# MCU.net
KiCad netlist of a schematic drawn in Altium Designer
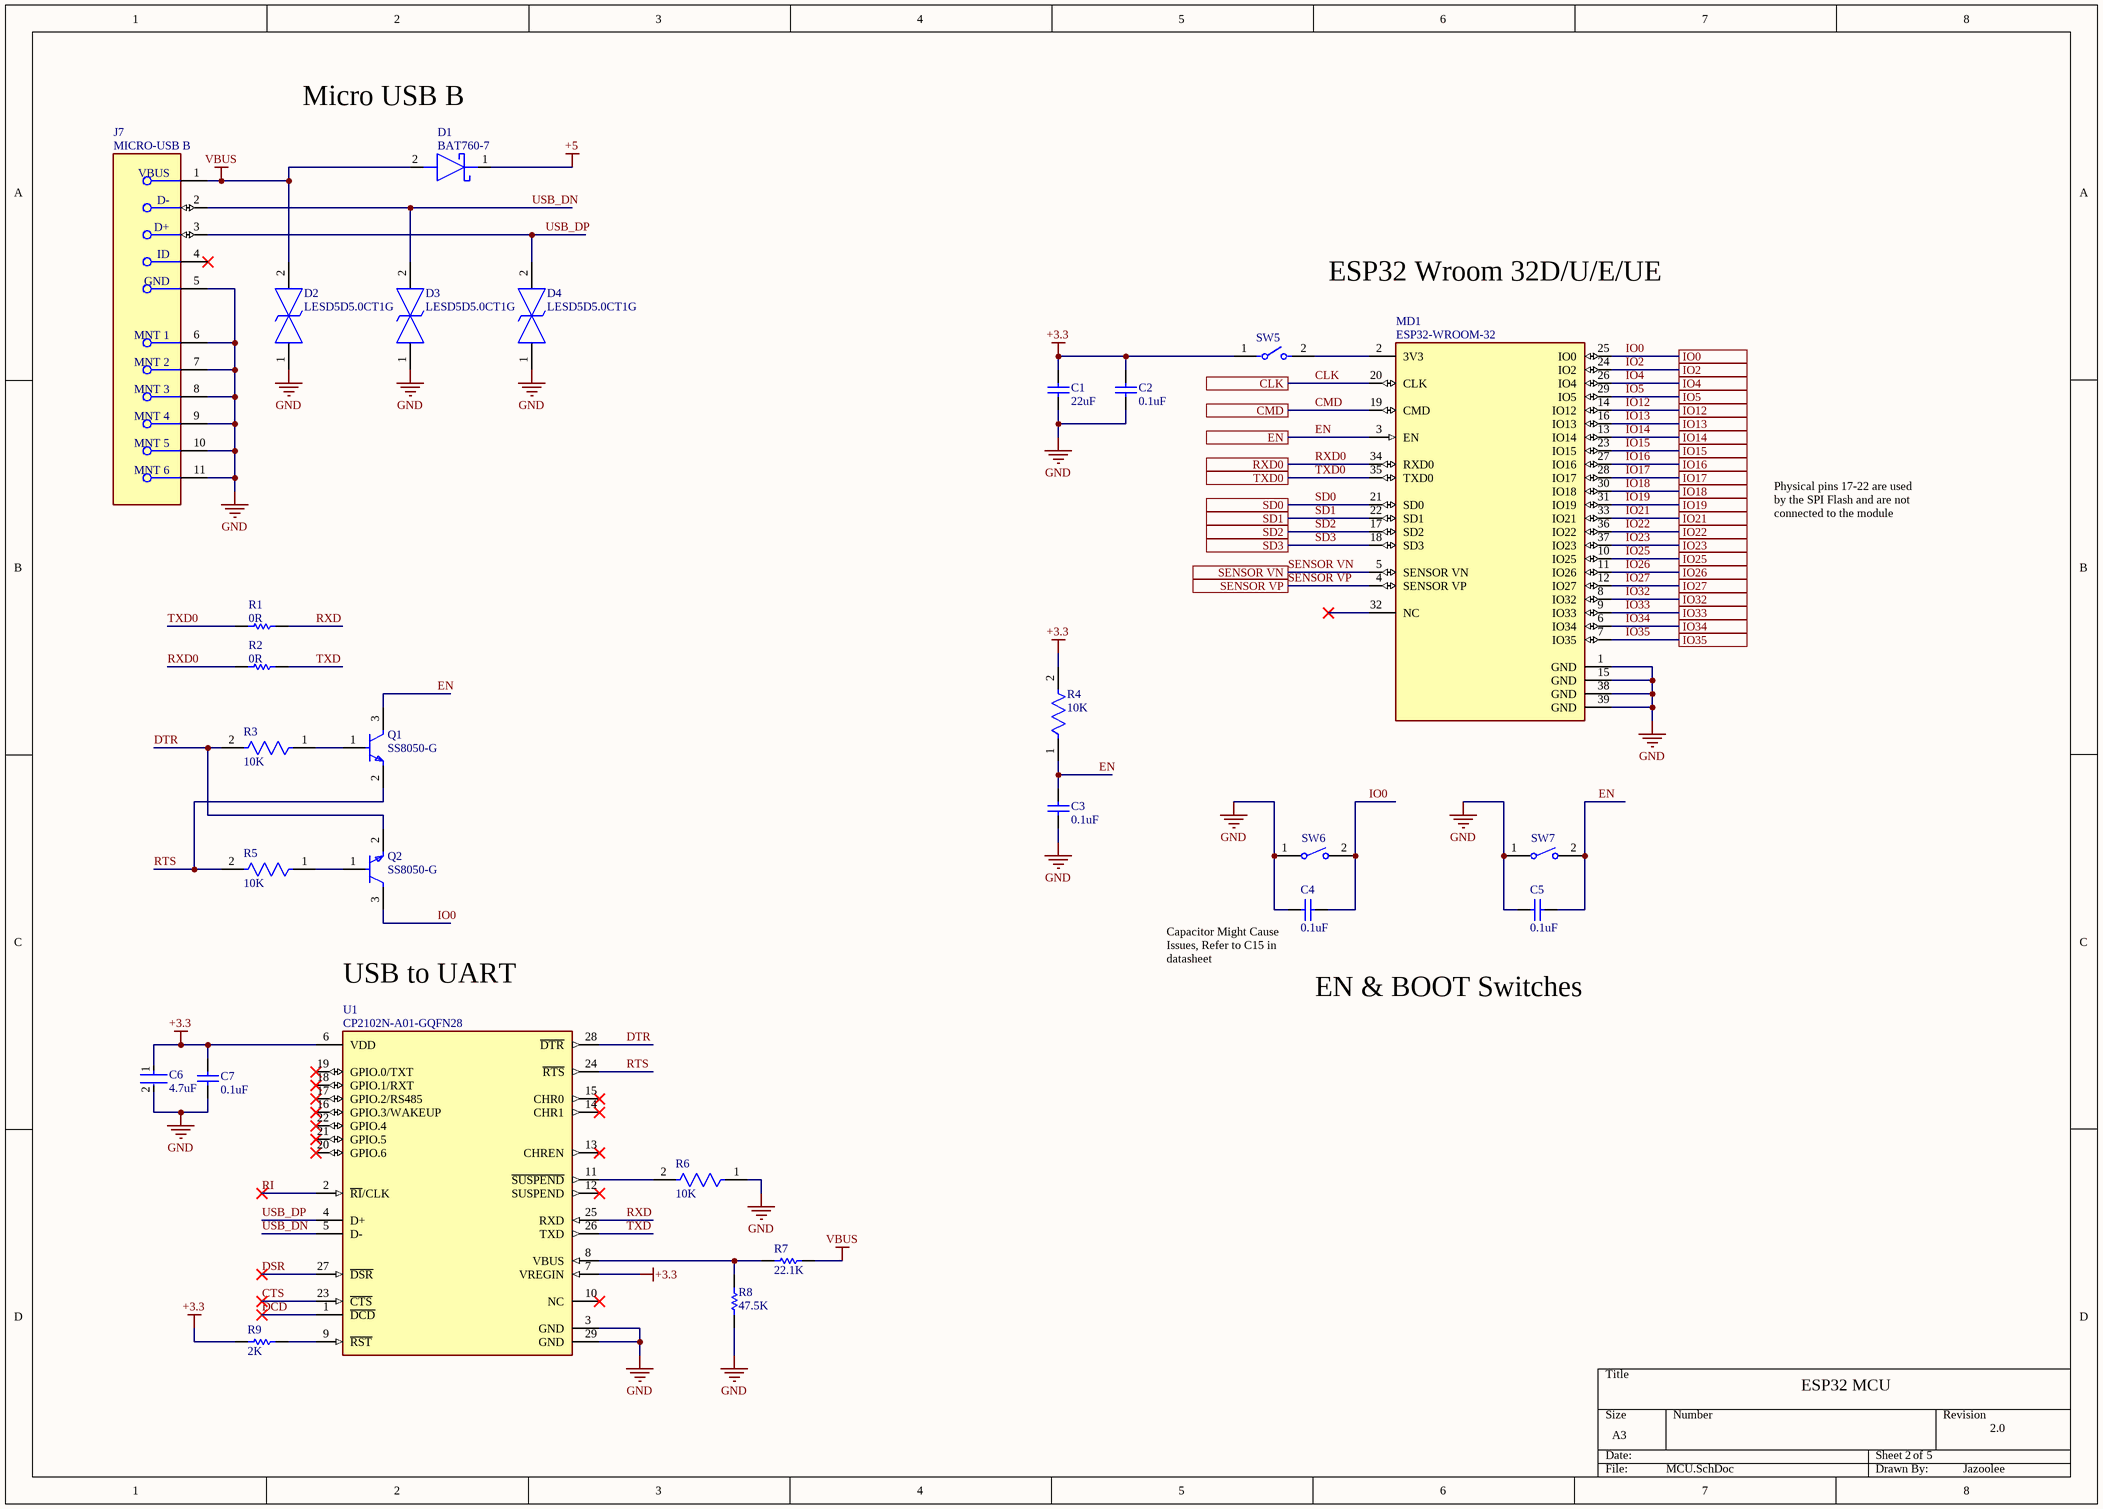
[diagram p0: MCU.SchDoc]

(export (version "E")
  (design (tool "Eeschema 10.0.6"))
  (components
    (comp (ref "C1")
      (value "22uF")
      (footprint "CAPC2014X150X70ML20")
      (description "22uF 10V 20% Tantalum 0805")
      (fields
        (field (name "PART NUMBER") "TACR226M010XTA")
        (field (name "MANUFACTURER") "AVX Interconnect / Elco")
      )
      (libsource (lib "Altium Content Vault") (part "CAP"))
    )
    (comp (ref "C2")
      (value "0.1uF")
      (footprint "CAPC2013X140X50LL20T25")
      (description "100nF 0805 Ceramic 50V 10%")
      (fields
        (field (name "MANUFACTURER") "AVX Interconnect / Elco")
        (field (name "PART NUMBER") "08055F104KAT2A")
      )
      (libsource (lib "Altium Content Vault") (part "CAP"))
    )
    (comp (ref "C3")
      (value "0.1uF")
      (footprint "CAPC2013X140X50LL20T25")
      (description "100nF 0805 Ceramic 50V 10%")
      (fields
        (field (name "MANUFACTURER") "AVX Interconnect / Elco")
        (field (name "PART NUMBER") "08055F104KAT2A")
      )
      (libsource (lib "Altium Content Vault") (part "CAP"))
    )
    (comp (ref "C4")
      (value "0.1uF")
      (footprint "CAPC2013X140X50LL20T25")
      (description "100nF 0805 Ceramic 50V 10%")
      (fields
        (field (name "MANUFACTURER") "AVX Interconnect / Elco")
        (field (name "PART NUMBER") "08055F104KAT2A")
      )
      (libsource (lib "Altium Content Vault") (part "CAP"))
    )
    (comp (ref "C5")
      (value "0.1uF")
      (footprint "CAPC2013X140X50LL20T25")
      (description "100nF 0805 Ceramic 50V 10%")
      (fields
        (field (name "MANUFACTURER") "AVX Interconnect / Elco")
        (field (name "PART NUMBER") "08055F104KAT2A")
      )
      (libsource (lib "Altium Content Vault") (part "CAP"))
    )
    (comp (ref "C6")
      (value "CL21A475KQFNNNF")
      (footprint "FP-CL21-IPC_B")
      (description "CL21 Series 0805 4.7uF 6.3V ±10% Tolerance X5R Multilayer Ceramic Chip Capacitor")
      (fields (field (name "CAPACITANCE") "4.7uF") (field (name "TOLERANCE") "10%"))
      (libsource (lib "Altium Content Vault") (part "b4654b650e69147ec39a6b967a45e02"))
    )
    (comp (ref "C7")
      (value "0.1uF")
      (footprint "CAPC2013X140X50LL20T25")
      (description "100nF 0805 Ceramic 50V 10%")
      (fields
        (field (name "MANUFACTURER") "AVX Interconnect / Elco")
        (field (name "PART NUMBER") "08055F104KAT2A")
      )
      (libsource (lib "Altium Content Vault") (part "CAP"))
    )
    (comp (ref "D1")
      (value "BAT760-7")
      (footprint "SamacSys:SOD2512X110N")
      (description "Schottky Diode")
      (fields
        (field (name "MANUFACTURER_PART_NUMBER") "BAT760,115")
        (field (name "MOUSER PART NUMBER") "771-BAT760-T/R")
      )
      (libsource (lib "*") (part "BAT760,115"))
    )
    (comp (ref "D2")
      (value "LESD5D5.0CT1G")
      (footprint "SamacSys:LESD5D50CT1G")
      (description "TVS Diode (Bi-directional)")
      (libsource (lib "SamacSys") (part "LESD5D5.0CT1G"))
    )
    (comp (ref "D3")
      (value "LESD5D5.0CT1G")
      (footprint "SamacSys:LESD5D50CT1G")
      (description "TVS Diode (Bi-directional)")
      (libsource (lib "SamacSys") (part "LESD5D5.0CT1G"))
    )
    (comp (ref "D4")
      (value "LESD5D5.0CT1G")
      (footprint "SamacSys:LESD5D50CT1G")
      (description "TVS Diode (Bi-directional)")
      (libsource (lib "SamacSys") (part "LESD5D5.0CT1G"))
    )
    (comp (ref "J7")
      (value "MICRO-USB B")
      (footprint "FP-473460001-MFG")
      (description "USB - micro B USB 2.0 Receptacle Connector 5 Position Surface Mount, Right Angle")
      (fields (field (name "OCTOPART") "https://octopart.com/47346-0001-molex-7164928"))
      (libsource (lib "Altium Content Vault") (part "53ae1f1d9b557310b43ca686e5bb76a"))
    )
    (comp (ref "MD1")
      (value "ESP32-WROOM-32")
      (footprint "FP-ESP32-WROOM-32-MFG")
      (description "RX TXRX MOD WIFI SURFACE MOUNT")
      (libsource (lib "Altium Content Vault") (part "ee866abf0b6c51247b7f5cdebf2f250"))
    )
    (comp (ref "Q1")
      (value "SS8050-G")
      (footprint "FP-SS8050-G-MFG")
      (description "NPN TRANSISTOR 1.5A 40V SOT-23 R")
      (libsource (lib "Altium Content Vault") (part "2a1388f82443b098dcd57d24ac7632d"))
    )
    (comp (ref "Q2")
      (value "SS8050-G")
      (footprint "FP-SS8050-G-MFG")
      (description "NPN TRANSISTOR 1.5A 40V SOT-23 R")
      (libsource (lib "Altium Content Vault") (part "2a1388f82443b098dcd57d24ac7632d"))
    )
    (comp (ref "R1")
      (value "0R")
      (footprint "RESC2013X60X35LL10T20")
      (description "Chip Resistor, 0 Ohm, +/- 5%, 125 mW, -55 to 155 degC, 0805 (2012 Metric), RoHS, Tape and Reel")
      (fields (field (name "MANUFACTURER") "Yageo") (field (name "Comment") "RC0805JR-100RL"))
      (libsource (lib "Altium Content Vault") (part "RES-2"))
    )
    (comp (ref "R2")
      (value "0R")
      (footprint "RESC2013X60X35LL10T20")
      (description "Chip Resistor, 0 Ohm, +/- 5%, 125 mW, -55 to 155 degC, 0805 (2012 Metric), RoHS, Tape and Reel")
      (fields (field (name "MANUFACTURER") "Yageo") (field (name "Comment") "RC0805JR-100RL"))
      (libsource (lib "Altium Content Vault") (part "RES-2"))
    )
    (comp (ref "R3")
      (value "RMCF0805JT10K0")
      (footprint "FP-RMCF0805-IPC_A")
      (description "10kΩ ±5% 0.125W 0805 Thick Film Chip Resistor AEC-Q200 compliant")
      (fields (field (name "RESISTANCE") "10K") (field (name "TOLERANCE") "5%"))
      (libsource (lib "Altium Content Vault") (part "1029c3af85768c4190bb7ad29bc67b5"))
    )
    (comp (ref "R4")
      (value "RMCF0805JT10K0")
      (footprint "FP-RMCF0805-IPC_A")
      (description "10kΩ ±5% 0.125W 0805 Thick Film Chip Resistor AEC-Q200 compliant")
      (fields (field (name "RESISTANCE") "10K") (field (name "TOLERANCE") "5%"))
      (libsource (lib "Altium Content Vault") (part "1029c3af85768c4190bb7ad29bc67b5"))
    )
    (comp (ref "R5")
      (value "RMCF0805JT10K0")
      (footprint "FP-RMCF0805-IPC_A")
      (description "10kΩ ±5% 0.125W 0805 Thick Film Chip Resistor AEC-Q200 compliant")
      (fields (field (name "RESISTANCE") "10K") (field (name "TOLERANCE") "5%"))
      (libsource (lib "Altium Content Vault") (part "1029c3af85768c4190bb7ad29bc67b5"))
    )
    (comp (ref "R6")
      (value "RMCF0805JT10K0")
      (footprint "FP-RMCF0805-IPC_A")
      (description "10kΩ ±5% 0.125W 0805 Thick Film Chip Resistor AEC-Q200 compliant")
      (fields (field (name "RESISTANCE") "10K") (field (name "TOLERANCE") "5%"))
      (libsource (lib "Altium Content Vault") (part "1029c3af85768c4190bb7ad29bc67b5"))
    )
    (comp (ref "R7")
      (value "22.1K")
      (footprint "RESC2013X50X30LL20T20")
      (description "22.1K 0805 5%")
      (fields (field (name "MANUFACTURER") "Vishay Dale") (field (name "PART NUMBER") "CRCW080522K1FKTA"))
      (libsource (lib "Altium Content Vault") (part "RES"))
    )
    (comp (ref "R8")
      (value "47.5K")
      (footprint "RESC2013X70X40NL20T20")
      (description "47.5K 0805 5%")
      (fields (field (name "PART NUMBER") "ERJ-6ENF4752V") (field (name "MANUFACTURER") "Panasonic"))
      (libsource (lib "Altium Content Vault") (part "RES"))
    )
    (comp (ref "R9")
      (value "2K")
      (footprint "RESC2013X60X35LL10T20")
      (fields (field (name "PART NUMBER") "RT0805FRE072KL") (field (name "MANUFACTURER") "Yageo"))
      (libsource (lib "Altium Content Vault") (part "RES"))
    )
    (comp (ref "SW5")
      (value "BD01")
      (footprint "FP-BD01-MFG")
      (description "SWITCH SLIDE DIP SPST 100MA 5V")
      (libsource (lib "Altium Content Vault") (part "bb27bde45df87f1f469753f287ef5ae"))
    )
    (comp (ref "SW6")
      (value "FSMSM")
      (footprint "TECO-FSMSM-2_V")
      (description "FSMSM Push Button Switch, 50 mA, -35 to 85 degC, 2-Pin SMD, RoHS, Bulk")
      (fields (field (name "MANUFACTURER") "TE Connectivity"))
      (libsource (lib "Altium Content Vault") (part "SW-SPST-2_C"))
    )
    (comp (ref "SW7")
      (value "FSMSM")
      (footprint "TECO-FSMSM-2_V")
      (description "FSMSM Push Button Switch, 50 mA, -35 to 85 degC, 2-Pin SMD, RoHS, Bulk")
      (fields (field (name "MANUFACTURER") "TE Connectivity"))
      (libsource (lib "Altium Content Vault") (part "SW-SPST-2_C"))
    )
    (comp (ref "U1")
      (value "CP2102N-A01-GQFN28")
      (footprint "FP-CP2102N-A01-GQFN28-MFG")
      (description "IC BRIDGE USB TO UART 28QFN")
      (fields
        (field (name "MANUFACTURER") "Silicon Labs")
        (field (name "OCTOPART") "https://octopart.com/cp2102n-a01-gqfn28-silicon+labs-74636024")
      )
      (libsource (lib "Altium Content Vault") (part "9ca185fe47a6ee51fa7191d999467af"))
    )
  )
  (nets
    (net (code "1") (name "+3.3") (class "Default")
      (node (ref "C1") (pin "2") (pinfunction "2_2") (pintype "passive"))
      (node (ref "C2") (pin "2") (pinfunction "2_2") (pintype "passive"))
      (node (ref "C6") (pin "1") (pinfunction "1_1") (pintype "passive"))
      (node (ref "C7") (pin "2") (pinfunction "2_2") (pintype "passive"))
      (node (ref "R4") (pin "2") (pinfunction "2_2") (pintype "passive"))
      (node (ref "R9") (pin "2") (pinfunction "2_2") (pintype "passive"))
      (node (ref "SW5") (pin "1") (pinfunction "1_1") (pintype "passive"))
      (node (ref "U1") (pin "6") (pinfunction "VDD_6") (pintype "power_in"))
      (node (ref "U1") (pin "7") (pinfunction "VREGIN_7") (pintype "input"))
    )
    (net (code "2") (name "+5") (class "Default")
      (node (ref "D1") (pin "1") (pinfunction "K_1") (pintype "passive"))
    )
    (net (code "3") (name "/CLK") (class "Default")
      (node (ref "MD1") (pin "20") (pinfunction "CLK_20") (pintype "bidirectional"))
    )
    (net (code "4") (name "/CMD") (class "Default")
      (node (ref "MD1") (pin "19") (pinfunction "CMD_19") (pintype "bidirectional"))
    )
    (net (code "5") (name "/CTS") (class "Default")
      (node (ref "U1") (pin "23") (pinfunction "~{CTS}_23") (pintype "input+no_connect"))
    )
    (net (code "6") (name "/DCD") (class "Default")
      (node (ref "U1") (pin "1") (pinfunction "~{DCD}_1") (pintype "passive+no_connect"))
    )
    (net (code "7") (name "/DSR") (class "Default")
      (node (ref "U1") (pin "27") (pinfunction "~{DSR}_27") (pintype "input+no_connect"))
    )
    (net (code "8") (name "/DTR") (class "Default")
      (node (ref "Q2") (pin "2") (pinfunction "E_2") (pintype "passive"))
      (node (ref "R3") (pin "2") (pinfunction "2_2") (pintype "passive"))
      (node (ref "U1") (pin "28") (pinfunction "~{DTR}_28") (pintype "output"))
    )
    (net (code "9") (name "/EN") (class "Default")
      (node (ref "C3") (pin "2") (pinfunction "2_2") (pintype "passive"))
      (node (ref "C5") (pin "1") (pinfunction "1_1") (pintype "passive"))
      (node (ref "MD1") (pin "3") (pinfunction "EN_3") (pintype "input"))
      (node (ref "Q1") (pin "3") (pinfunction "C_3") (pintype "passive"))
      (node (ref "R4") (pin "1") (pinfunction "1_1") (pintype "passive"))
      (node (ref "SW7") (pin "2") (pinfunction "2_2") (pintype "passive"))
    )
    (net (code "10") (name "/IO0") (class "Default")
      (node (ref "C4") (pin "1") (pinfunction "1_1") (pintype "passive"))
      (node (ref "MD1") (pin "25") (pinfunction "IO0_25") (pintype "bidirectional"))
      (node (ref "Q2") (pin "3") (pinfunction "C_3") (pintype "passive"))
      (node (ref "SW6") (pin "2") (pinfunction "2_2") (pintype "passive"))
    )
    (net (code "11") (name "/IO2") (class "Default")
      (node (ref "MD1") (pin "24") (pinfunction "IO2_24") (pintype "bidirectional"))
    )
    (net (code "12") (name "/IO4") (class "Default")
      (node (ref "MD1") (pin "26") (pinfunction "IO4_26") (pintype "bidirectional"))
    )
    (net (code "13") (name "/IO5") (class "Default")
      (node (ref "MD1") (pin "29") (pinfunction "IO5_29") (pintype "bidirectional"))
    )
    (net (code "14") (name "/IO12") (class "Default")
      (node (ref "MD1") (pin "14") (pinfunction "IO12_14") (pintype "bidirectional"))
    )
    (net (code "15") (name "/IO13") (class "Default")
      (node (ref "MD1") (pin "16") (pinfunction "IO13_16") (pintype "bidirectional"))
    )
    (net (code "16") (name "/IO14") (class "Default")
      (node (ref "MD1") (pin "13") (pinfunction "IO14_13") (pintype "bidirectional"))
    )
    (net (code "17") (name "/IO15") (class "Default")
      (node (ref "MD1") (pin "23") (pinfunction "IO15_23") (pintype "bidirectional"))
    )
    (net (code "18") (name "/IO16") (class "Default")
      (node (ref "MD1") (pin "27") (pinfunction "IO16_27") (pintype "bidirectional"))
    )
    (net (code "19") (name "/IO17") (class "Default")
      (node (ref "MD1") (pin "28") (pinfunction "IO17_28") (pintype "bidirectional"))
    )
    (net (code "20") (name "/IO18") (class "Default")
      (node (ref "MD1") (pin "30") (pinfunction "IO18_30") (pintype "bidirectional"))
    )
    (net (code "21") (name "/IO19") (class "Default")
      (node (ref "MD1") (pin "31") (pinfunction "IO19_31") (pintype "bidirectional"))
    )
    (net (code "22") (name "/IO21") (class "Default")
      (node (ref "MD1") (pin "33") (pinfunction "IO21_33") (pintype "bidirectional"))
    )
    (net (code "23") (name "/IO22") (class "Default")
      (node (ref "MD1") (pin "36") (pinfunction "IO22_36") (pintype "bidirectional"))
    )
    (net (code "24") (name "/IO23") (class "Default")
      (node (ref "MD1") (pin "37") (pinfunction "IO23_37") (pintype "bidirectional"))
    )
    (net (code "25") (name "/IO25") (class "Default")
      (node (ref "MD1") (pin "10") (pinfunction "IO25_10") (pintype "bidirectional"))
    )
    (net (code "26") (name "/IO26") (class "Default")
      (node (ref "MD1") (pin "11") (pinfunction "IO26_11") (pintype "bidirectional"))
    )
    (net (code "27") (name "/IO27") (class "Default")
      (node (ref "MD1") (pin "12") (pinfunction "IO27_12") (pintype "bidirectional"))
    )
    (net (code "28") (name "/IO32") (class "Default")
      (node (ref "MD1") (pin "8") (pinfunction "IO32_8") (pintype "bidirectional"))
    )
    (net (code "29") (name "/IO33") (class "Default")
      (node (ref "MD1") (pin "9") (pinfunction "IO33_9") (pintype "bidirectional"))
    )
    (net (code "30") (name "/IO34") (class "Default")
      (node (ref "MD1") (pin "6") (pinfunction "IO34_6") (pintype "bidirectional"))
    )
    (net (code "31") (name "/IO35") (class "Default")
      (node (ref "MD1") (pin "7") (pinfunction "IO35_7") (pintype "bidirectional"))
    )
    (net (code "32") (name "/RI") (class "Default")
      (node (ref "U1") (pin "2") (pinfunction "~{RI}/CLK_2") (pintype "input+no_connect"))
    )
    (net (code "33") (name "/RTS") (class "Default")
      (node (ref "Q1") (pin "2") (pinfunction "E_2") (pintype "passive"))
      (node (ref "R5") (pin "2") (pinfunction "2_2") (pintype "passive"))
      (node (ref "U1") (pin "24") (pinfunction "~{RTS}_24") (pintype "output"))
    )
    (net (code "34") (name "/RXD") (class "Default")
      (node (ref "R1") (pin "2") (pinfunction "2_2") (pintype "passive"))
      (node (ref "U1") (pin "25") (pinfunction "RXD_25") (pintype "input"))
    )
    (net (code "35") (name "/RXD0") (class "Default")
      (node (ref "MD1") (pin "34") (pinfunction "RXD0_34") (pintype "bidirectional"))
      (node (ref "R2") (pin "1") (pinfunction "1_1") (pintype "passive"))
    )
    (net (code "36") (name "/SD0") (class "Default")
      (node (ref "MD1") (pin "21") (pinfunction "SD0_21") (pintype "bidirectional"))
    )
    (net (code "37") (name "/SD1") (class "Default")
      (node (ref "MD1") (pin "22") (pinfunction "SD1_22") (pintype "bidirectional"))
    )
    (net (code "38") (name "/SD2") (class "Default")
      (node (ref "MD1") (pin "17") (pinfunction "SD2_17") (pintype "bidirectional"))
    )
    (net (code "39") (name "/SD3") (class "Default")
      (node (ref "MD1") (pin "18") (pinfunction "SD3_18") (pintype "bidirectional"))
    )
    (net (code "40") (name "/SENSOR VN") (class "Default")
      (node (ref "MD1") (pin "5") (pinfunction "SENSOR_VN_5") (pintype "bidirectional"))
    )
    (net (code "41") (name "/SENSOR VP") (class "Default")
      (node (ref "MD1") (pin "4") (pinfunction "SENSOR_VP_4") (pintype "bidirectional"))
    )
    (net (code "42") (name "/TXD") (class "Default")
      (node (ref "R2") (pin "2") (pinfunction "2_2") (pintype "passive"))
      (node (ref "U1") (pin "26") (pinfunction "TXD_26") (pintype "output"))
    )
    (net (code "43") (name "/TXD0") (class "Default")
      (node (ref "MD1") (pin "35") (pinfunction "TXD0_35") (pintype "bidirectional"))
      (node (ref "R1") (pin "1") (pinfunction "1_1") (pintype "passive"))
    )
    (net (code "44") (name "/USB_DN") (class "Default")
      (node (ref "D3") (pin "2") (pinfunction "2_2") (pintype "passive"))
      (node (ref "J7") (pin "2") (pinfunction "D-_2") (pintype "bidirectional"))
      (node (ref "U1") (pin "5") (pinfunction "D-_5") (pintype "passive"))
    )
    (net (code "45") (name "/USB_DP") (class "Default")
      (node (ref "D4") (pin "2") (pinfunction "2_2") (pintype "passive"))
      (node (ref "J7") (pin "3") (pinfunction "D+_3") (pintype "bidirectional"))
      (node (ref "U1") (pin "4") (pinfunction "D+_4") (pintype "passive"))
    )
    (net (code "46") (name "GND") (class "Default")
      (node (ref "C1") (pin "1") (pinfunction "1_1") (pintype "passive"))
      (node (ref "C2") (pin "1") (pinfunction "1_1") (pintype "passive"))
      (node (ref "C3") (pin "1") (pinfunction "1_1") (pintype "passive"))
      (node (ref "C4") (pin "2") (pinfunction "2_2") (pintype "passive"))
      (node (ref "C5") (pin "2") (pinfunction "2_2") (pintype "passive"))
      (node (ref "C6") (pin "2") (pinfunction "2_2") (pintype "passive"))
      (node (ref "C7") (pin "1") (pinfunction "1_1") (pintype "passive"))
      (node (ref "D2") (pin "1") (pinfunction "1_1") (pintype "passive"))
      (node (ref "D3") (pin "1") (pinfunction "1_1") (pintype "passive"))
      (node (ref "D4") (pin "1") (pinfunction "1_1") (pintype "passive"))
      (node (ref "J7") (pin "10") (pinfunction "MNT_5_10") (pintype "passive"))
      (node (ref "J7") (pin "11") (pinfunction "MNT_6_11") (pintype "passive"))
      (node (ref "J7") (pin "5") (pinfunction "GND_5") (pintype "power_in"))
      (node (ref "J7") (pin "6") (pinfunction "MNT_1_6") (pintype "passive"))
      (node (ref "J7") (pin "7") (pinfunction "MNT_2_7") (pintype "passive"))
      (node (ref "J7") (pin "8") (pinfunction "MNT_3_8") (pintype "passive"))
      (node (ref "J7") (pin "9") (pinfunction "MNT_4_9") (pintype "passive"))
      (node (ref "MD1") (pin "1") (pinfunction "GND_1") (pintype "power_in"))
      (node (ref "MD1") (pin "15") (pinfunction "GND_15") (pintype "power_in"))
      (node (ref "MD1") (pin "38") (pinfunction "GND_38") (pintype "power_in"))
      (node (ref "MD1") (pin "39") (pinfunction "GND_39") (pintype "power_in"))
      (node (ref "R6") (pin "1") (pinfunction "1_1") (pintype "passive"))
      (node (ref "R8") (pin "1") (pinfunction "1_1") (pintype "passive"))
      (node (ref "SW6") (pin "1") (pinfunction "1_1") (pintype "passive"))
      (node (ref "SW7") (pin "1") (pinfunction "1_1") (pintype "passive"))
      (node (ref "U1") (pin "29") (pinfunction "GND_29") (pintype "power_in"))
      (node (ref "U1") (pin "3") (pinfunction "GND_3") (pintype "power_in"))
    )
    (net (code "47") (name "Net-(MD1-3V3)") (class "Default")
      (node (ref "MD1") (pin "2") (pinfunction "3V3_2") (pintype "power_in"))
      (node (ref "SW5") (pin "2") (pinfunction "2_2") (pintype "passive"))
    )
    (net (code "48") (name "Net-(Q1-B)") (class "Default")
      (node (ref "Q1") (pin "1") (pinfunction "B_1") (pintype "passive"))
      (node (ref "R3") (pin "1") (pinfunction "1_1") (pintype "passive"))
    )
    (net (code "49") (name "Net-(Q2-B)") (class "Default")
      (node (ref "Q2") (pin "1") (pinfunction "B_1") (pintype "passive"))
      (node (ref "R5") (pin "1") (pinfunction "1_1") (pintype "passive"))
    )
    (net (code "50") (name "Net-(U1-VBUS)") (class "Default")
      (node (ref "R7") (pin "2") (pinfunction "2_2") (pintype "passive"))
      (node (ref "R8") (pin "2") (pinfunction "2_2") (pintype "passive"))
      (node (ref "U1") (pin "8") (pinfunction "VBUS_8") (pintype "input"))
    )
    (net (code "51") (name "Net-(U1-~{RST})") (class "Default")
      (node (ref "R9") (pin "1") (pinfunction "1_1") (pintype "passive"))
      (node (ref "U1") (pin "9") (pinfunction "~{RST}_9") (pintype "input"))
    )
    (net (code "52") (name "Net-(U1-~{SUSPEND})") (class "Default")
      (node (ref "R6") (pin "2") (pinfunction "2_2") (pintype "passive"))
      (node (ref "U1") (pin "11") (pinfunction "~{SUSPEND}_11") (pintype "output"))
    )
    (net (code "53") (name "VBUS") (class "Default")
      (node (ref "D1") (pin "2") (pinfunction "A_2") (pintype "passive"))
      (node (ref "D2") (pin "2") (pinfunction "2_2") (pintype "passive"))
      (node (ref "J7") (pin "1") (pinfunction "VBUS_1") (pintype "power_in"))
      (node (ref "R7") (pin "1") (pinfunction "1_1") (pintype "passive"))
    )
    (net (code "54") (name "unconnected-(J7-ID-Pad4)") (class "Default")
      (node (ref "J7") (pin "4") (pinfunction "ID_4") (pintype "passive+no_connect"))
    )
    (net (code "55") (name "unconnected-(MD1-NC-Pad32)") (class "Default")
      (node (ref "MD1") (pin "32") (pinfunction "NC_32") (pintype "passive+no_connect"))
    )
    (net (code "56") (name "unconnected-(U1-CHR0-Pad15)") (class "Default")
      (node (ref "U1") (pin "15") (pinfunction "CHR0_15") (pintype "output+no_connect"))
    )
    (net (code "57") (name "unconnected-(U1-CHR1-Pad14)") (class "Default")
      (node (ref "U1") (pin "14") (pinfunction "CHR1_14") (pintype "output+no_connect"))
    )
    (net (code "58") (name "unconnected-(U1-CHREN-Pad13)") (class "Default")
      (node (ref "U1") (pin "13") (pinfunction "CHREN_13") (pintype "output+no_connect"))
    )
    (net (code "59") (name "unconnected-(U1-GPIO.0{slash}TXT-Pad19)") (class "Default")
      (node (ref "U1") (pin "19") (pinfunction "GPIO.0/TXT_19") (pintype "bidirectional+no_connect"))
    )
    (net (code "60") (name "unconnected-(U1-GPIO.1{slash}RXT-Pad18)") (class "Default")
      (node (ref "U1") (pin "18") (pinfunction "GPIO.1/RXT_18") (pintype "bidirectional+no_connect"))
    )
    (net (code "61") (name "unconnected-(U1-GPIO.2{slash}RS485-Pad17)") (class "Default")
      (node (ref "U1") (pin "17") (pinfunction "GPIO.2/RS485_17") (pintype "bidirectional+no_connect"))
    )
    (net (code "62") (name "unconnected-(U1-GPIO.3{slash}WAKEUP-Pad16)") (class "Default")
      (node (ref "U1") (pin "16") (pinfunction "GPIO.3/WAKEUP_16") (pintype "bidirectional+no_connect"))
    )
    (net (code "63") (name "unconnected-(U1-GPIO.4-Pad22)") (class "Default")
      (node (ref "U1") (pin "22") (pinfunction "GPIO.4_22") (pintype "bidirectional+no_connect"))
    )
    (net (code "64") (name "unconnected-(U1-GPIO.5-Pad21)") (class "Default")
      (node (ref "U1") (pin "21") (pinfunction "GPIO.5_21") (pintype "bidirectional+no_connect"))
    )
    (net (code "65") (name "unconnected-(U1-GPIO.6-Pad20)") (class "Default")
      (node (ref "U1") (pin "20") (pinfunction "GPIO.6_20") (pintype "bidirectional+no_connect"))
    )
    (net (code "66") (name "unconnected-(U1-NC-Pad10)") (class "Default")
      (node (ref "U1") (pin "10") (pinfunction "NC_10") (pintype "passive+no_connect"))
    )
    (net (code "67") (name "unconnected-(U1-SUSPEND-Pad12)") (class "Default")
      (node (ref "U1") (pin "12") (pinfunction "SUSPEND_12") (pintype "output+no_connect"))
    )
  )
)
